# MAIN.net
KiCad netlist of a schematic drawn in Altium Designer
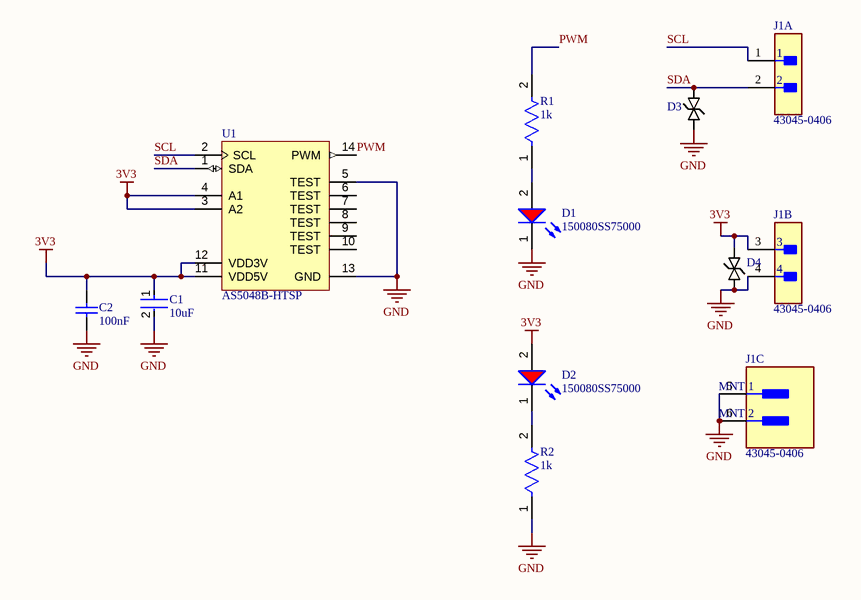
[diagram p0: MAIN.SchDoc]

(export (version "E")
  (design (tool "Eeschema 10.0.6"))
  (components
    (comp (ref "C1")
      (value "10uF")
      (footprint "FP-GRM188-0_1-e0_2_0_55-IPC_A")
      (description "Chip Multilayer Ceramic Capacitors for General Purpose, 0603, 10uF, X5R, 15%, 20%, 6.3V")
      (fields (field (name "VOLTAGE") "6.3V") (field (name "TOLERANCE") "20%"))
      (libsource (lib "Altium Content Vault") (part "02cd4be3c70576c341d710602a673aa"))
    )
    (comp (ref "C2")
      (value "100nF")
      (footprint "CAPC2013X140X50ML20T25")
      (fields
        (field (name "MANUFACTURER") "AVX Interconnect / Elco")
        (field (name "PART NUMBER") "08055F104KAT2A")
      )
      (libsource (lib "Altium Content Vault") (part "CAP"))
    )
    (comp (ref "D1")
      (value "150080SS75000")
      (footprint "WL-SMCW_0805_150080xx75000")
      (description "Led, Red, 630 Nm, 1.9 V, 30 Ma, 60 Mcd Rohs Compliant: Yes")
      (libsource (lib "Altium Content Vault") (part "LED_Red_2A-1K"))
    )
    (comp (ref "D2")
      (value "150080SS75000")
      (footprint "WL-SMCW_0805_150080xx75000")
      (description "Led, Red, 630 Nm, 1.9 V, 30 Ma, 60 Mcd Rohs Compliant: Yes")
      (libsource (lib "Altium Content Vault") (part "LED_Red_2A-1K"))
    )
    (comp (ref "D3")
      (value "ESDULC3V3D5B-TP")
      (footprint "SODFL160X65-2N")
      (description "ESD Protection Diodes / TVS Diodes ESD,3.3V,SOD-523")
      (libsource (lib "tvs_diode") (part "tvs_diode"))
    )
    (comp (ref "D4")
      (value "ESDULC3V3D5B-TP")
      (footprint "SODFL160X65-2N")
      (description "ESD Protection Diodes / TVS Diodes ESD,3.3V,SOD-523")
      (libsource (lib "tvs_diode") (part "tvs_diode"))
    )
    (comp (ref "J1")
      (value "43045-0406")
      (footprint "FP-43045-0406-MFG")
      (description "CONN HEADER SMD R/A 4POS 3MM")
      (libsource (lib "Altium Content Vault") (part "58585532e1459b3b5fa8464169874db"))
    )
    (comp (ref "R1")
      (value "1k")
      (footprint "FP-RC0603-0_55-IPC_A")
      (description "RES 1K OHM 1% 1/10W 0603")
      (fields (field (name "TOLERANCE") "1%"))
      (libsource (lib "Altium Content Vault") (part "1029c3af85768c4190bb7ad29bc67b5"))
    )
    (comp (ref "R2")
      (value "1k")
      (footprint "FP-RC0603-0_55-IPC_A")
      (description "RES 1K OHM 1% 1/10W 0603")
      (fields (field (name "TOLERANCE") "1%"))
      (libsource (lib "Altium Content Vault") (part "1029c3af85768c4190bb7ad29bc67b5"))
    )
    (comp (ref "U1")
      (value "AS5048B-HTSP")
      (footprint "AMS-TSSOP-14-5000X4400DE_L")
      (description "Magnetic Rotary Encoder 14-bit Angular Position Sensor, 3.3 or 5 V, TSSOP-14, Pb-Free, Reel")
      (fields (field (name "MANUFACTURER") "AMS"))
      (libsource (lib "Altium Content Vault") (part "AMS-AS5048B-TSSOP-14"))
    )
  )
  (nets
    (net (code "1") (name "/PWM") (class "Default")
      (node (ref "R1") (pin "2") (pinfunction "2_2") (pintype "passive"))
      (node (ref "U1") (pin "14") (pinfunction "PWM_14") (pintype "output"))
    )
    (net (code "2") (name "/SCL") (class "Default")
      (node (ref "J1") (pin "1") (pinfunction "1_1") (pintype "passive"))
      (node (ref "U1") (pin "2") (pinfunction "SCL_2") (pintype "passive"))
    )
    (net (code "3") (name "/SDA") (class "Default")
      (node (ref "D3") (pin "2") (pinfunction "2_2") (pintype "passive"))
      (node (ref "J1") (pin "2") (pinfunction "2_2") (pintype "passive"))
      (node (ref "U1") (pin "1") (pinfunction "SDA_1") (pintype "bidirectional"))
    )
    (net (code "4") (name "3V3") (class "Default")
      (node (ref "C1") (pin "1") (pinfunction "1_1") (pintype "passive"))
      (node (ref "C2") (pin "2") (pinfunction "2_2") (pintype "passive"))
      (node (ref "D2") (pin "2") (pinfunction "A_2") (pintype "passive"))
      (node (ref "D4") (pin "2") (pinfunction "2_2") (pintype "passive"))
      (node (ref "J1") (pin "3") (pinfunction "3_3") (pintype "passive"))
      (node (ref "U1") (pin "11") (pinfunction "VDD5V_11") (pintype "power_in"))
      (node (ref "U1") (pin "12") (pinfunction "VDD3V_12") (pintype "power_in"))
      (node (ref "U1") (pin "3") (pinfunction "A2_3") (pintype "passive"))
      (node (ref "U1") (pin "4") (pinfunction "A1_4") (pintype "passive"))
    )
    (net (code "5") (name "GND") (class "Default")
      (node (ref "C1") (pin "2") (pinfunction "2_2") (pintype "passive"))
      (node (ref "C2") (pin "1") (pinfunction "1_1") (pintype "passive"))
      (node (ref "D1") (pin "1") (pinfunction "K_1") (pintype "passive"))
      (node (ref "D3") (pin "1") (pinfunction "1_1") (pintype "passive"))
      (node (ref "D4") (pin "1") (pinfunction "1_1") (pintype "passive"))
      (node (ref "J1") (pin "4") (pinfunction "4_4") (pintype "passive"))
      (node (ref "J1") (pin "5") (pinfunction "MNT_1_5") (pintype "passive"))
      (node (ref "J1") (pin "6") (pinfunction "MNT_2_6") (pintype "passive"))
      (node (ref "R2") (pin "1") (pinfunction "1_1") (pintype "passive"))
      (node (ref "U1") (pin "13") (pinfunction "GND_13") (pintype "power_in"))
      (node (ref "U1") (pin "5") (pinfunction "TEST_5") (pintype "passive"))
    )
    (net (code "6") (name "Net-(D1-A)") (class "Default")
      (node (ref "D1") (pin "2") (pinfunction "A_2") (pintype "passive"))
      (node (ref "R1") (pin "1") (pinfunction "1_1") (pintype "passive"))
    )
    (net (code "7") (name "Net-(D2-K)") (class "Default")
      (node (ref "D2") (pin "1") (pinfunction "K_1") (pintype "passive"))
      (node (ref "R2") (pin "2") (pinfunction "2_2") (pintype "passive"))
    )
    (net (code "8") (name "unconnected-(U1-TEST-Pad6)") (class "Default")
      (node (ref "U1") (pin "6") (pinfunction "TEST_6") (pintype "passive"))
    )
    (net (code "9") (name "unconnected-(U1-TEST-Pad7)") (class "Default")
      (node (ref "U1") (pin "7") (pinfunction "TEST_7") (pintype "passive"))
    )
    (net (code "10") (name "unconnected-(U1-TEST-Pad8)") (class "Default")
      (node (ref "U1") (pin "8") (pinfunction "TEST_8") (pintype "passive"))
    )
    (net (code "11") (name "unconnected-(U1-TEST-Pad9)") (class "Default")
      (node (ref "U1") (pin "9") (pinfunction "TEST_9") (pintype "passive"))
    )
    (net (code "12") (name "unconnected-(U1-TEST-Pad10)") (class "Default")
      (node (ref "U1") (pin "10") (pinfunction "TEST_10") (pintype "passive"))
    )
  )
)
